# Integration_board_3204.net
KiCad netlist of a schematic drawn in EAGLE
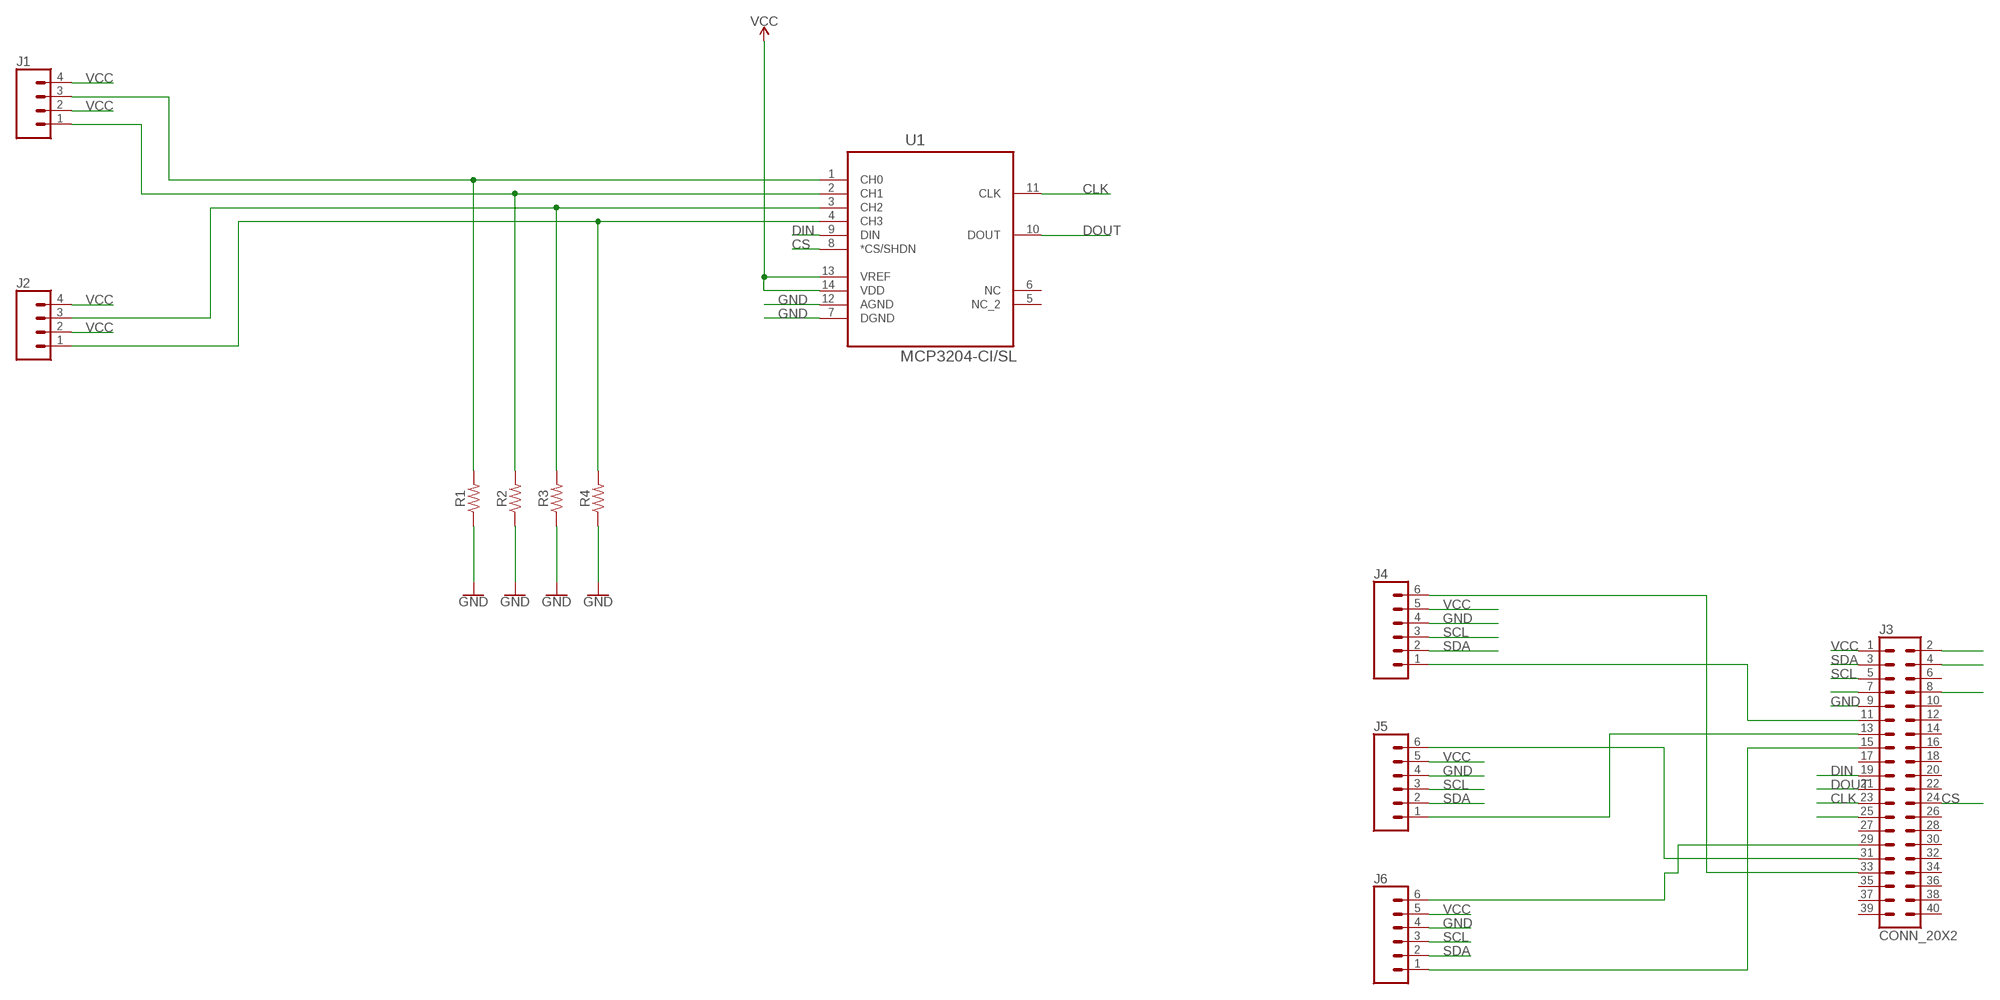
[diagram p0: schematic, sheet 1]

(export (version "E")
  (design (tool "Eeschema 10.0.6"))
  (components
    (comp (ref "J1")
      (value "CONN_04PTH")
      (footprint "eagle-import:1X04")
      (libsource (lib "eagle-import") (part "CONN_04PTH"))
    )
    (comp (ref "J2")
      (value "CONN_04PTH")
      (footprint "eagle-import:1X04")
      (libsource (lib "eagle-import") (part "CONN_04PTH"))
    )
    (comp (ref "J3")
      (value "CONN_20X2")
      (footprint "eagle-import:2X20")
      (libsource (lib "eagle-import") (part "CONN_20X2"))
    )
    (comp (ref "J4")
      (value "CONN_06SILK_FEMALE_PTH")
      (footprint "eagle-import:1X06")
      (libsource (lib "eagle-import") (part "CONN_06SILK_FEMALE_PTH"))
    )
    (comp (ref "J5")
      (value "CONN_06SILK_FEMALE_PTH")
      (footprint "eagle-import:1X06")
      (libsource (lib "eagle-import") (part "CONN_06SILK_FEMALE_PTH"))
    )
    (comp (ref "J6")
      (value "CONN_06SILK_FEMALE_PTH")
      (footprint "eagle-import:1X06")
      (libsource (lib "eagle-import") (part "CONN_06SILK_FEMALE_PTH"))
    )
    (comp (ref "R1")
      (value "RESISTORAXIAL-0.3")
      (footprint "eagle-import:AXIAL-0.3")
      (libsource (lib "eagle-import") (part "RESISTORAXIAL-0.3"))
    )
    (comp (ref "R2")
      (value "RESISTORAXIAL-0.3")
      (footprint "eagle-import:AXIAL-0.3")
      (libsource (lib "eagle-import") (part "RESISTORAXIAL-0.3"))
    )
    (comp (ref "R3")
      (value "RESISTORAXIAL-0.3")
      (footprint "eagle-import:AXIAL-0.3")
      (libsource (lib "eagle-import") (part "RESISTORAXIAL-0.3"))
    )
    (comp (ref "R4")
      (value "RESISTORAXIAL-0.3")
      (footprint "eagle-import:AXIAL-0.3")
      (libsource (lib "eagle-import") (part "RESISTORAXIAL-0.3"))
    )
    (comp (ref "U1")
      (value "MCP3204-CI/SL")
      (footprint "eagle-import:SOIC127P600X175-14N")
      (libsource (lib "eagle-import") (part "MCP3204-CI/SL"))
    )
  )
  (nets
    (net (code "1") (name "/CLK") (class "Default")
      (node (ref "J3") (pin "23") (pinfunction "23_23") (pintype "passive"))
      (node (ref "U1") (pin "11") (pinfunction "CLK_11") (pintype "input"))
    )
    (net (code "2") (name "/CS") (class "Default")
      (node (ref "J3") (pin "24") (pinfunction "24_24") (pintype "passive"))
      (node (ref "U1") (pin "8") (pinfunction "*CS/SHDN_8") (pintype "input"))
    )
    (net (code "3") (name "/DIN") (class "Default")
      (node (ref "J3") (pin "19") (pinfunction "19_19") (pintype "passive"))
      (node (ref "U1") (pin "9") (pinfunction "DIN_9") (pintype "input"))
    )
    (net (code "4") (name "/DOUT") (class "Default")
      (node (ref "J3") (pin "21") (pinfunction "21_21") (pintype "passive"))
      (node (ref "U1") (pin "10") (pinfunction "DOUT_10") (pintype "output"))
    )
    (net (code "5") (name "/SCL") (class "Default")
      (node (ref "J3") (pin "5") (pinfunction "5_5") (pintype "passive"))
      (node (ref "J4") (pin "3") (pinfunction "3_3") (pintype "passive"))
      (node (ref "J5") (pin "3") (pinfunction "3_3") (pintype "passive"))
      (node (ref "J6") (pin "3") (pinfunction "3_3") (pintype "passive"))
    )
    (net (code "6") (name "/SDA") (class "Default")
      (node (ref "J3") (pin "3") (pinfunction "3_3") (pintype "passive"))
      (node (ref "J4") (pin "2") (pinfunction "2_2") (pintype "passive"))
      (node (ref "J5") (pin "2") (pinfunction "2_2") (pintype "passive"))
      (node (ref "J6") (pin "2") (pinfunction "2_2") (pintype "passive"))
    )
    (net (code "7") (name "GND") (class "Default")
      (node (ref "J3") (pin "9") (pinfunction "9_9") (pintype "passive"))
      (node (ref "J4") (pin "4") (pinfunction "4_4") (pintype "passive"))
      (node (ref "J5") (pin "4") (pinfunction "4_4") (pintype "passive"))
      (node (ref "J6") (pin "4") (pinfunction "4_4") (pintype "passive"))
      (node (ref "R1") (pin "P$1") (pinfunction "1_P$1") (pintype "passive"))
      (node (ref "R2") (pin "P$1") (pinfunction "1_P$1") (pintype "passive"))
      (node (ref "R3") (pin "P$1") (pinfunction "1_P$1") (pintype "passive"))
      (node (ref "R4") (pin "P$1") (pinfunction "1_P$1") (pintype "passive"))
      (node (ref "U1") (pin "12") (pinfunction "AGND_12") (pintype "passive"))
      (node (ref "U1") (pin "7") (pinfunction "DGND_7") (pintype "passive"))
    )
    (net (code "8") (name "Net-(J3-Pad11)") (class "Default")
      (node (ref "J3") (pin "11") (pinfunction "11_11") (pintype "passive"))
      (node (ref "J4") (pin "1") (pinfunction "1_1") (pintype "passive"))
    )
    (net (code "9") (name "Net-(J3-Pad13)") (class "Default")
      (node (ref "J3") (pin "13") (pinfunction "13_13") (pintype "passive"))
      (node (ref "J5") (pin "1") (pinfunction "1_1") (pintype "passive"))
    )
    (net (code "10") (name "Net-(J3-Pad15)") (class "Default")
      (node (ref "J3") (pin "15") (pinfunction "15_15") (pintype "passive"))
      (node (ref "J6") (pin "1") (pinfunction "1_1") (pintype "passive"))
    )
    (net (code "11") (name "Net-(J3-Pad29)") (class "Default")
      (node (ref "J3") (pin "29") (pinfunction "29_29") (pintype "passive"))
      (node (ref "J6") (pin "6") (pinfunction "6_6") (pintype "passive"))
    )
    (net (code "12") (name "Net-(J3-Pad31)") (class "Default")
      (node (ref "J3") (pin "31") (pinfunction "31_31") (pintype "passive"))
      (node (ref "J5") (pin "6") (pinfunction "6_6") (pintype "passive"))
    )
    (net (code "13") (name "Net-(J3-Pad33)") (class "Default")
      (node (ref "J3") (pin "33") (pinfunction "33_33") (pintype "passive"))
      (node (ref "J4") (pin "6") (pinfunction "6_6") (pintype "passive"))
    )
    (net (code "14") (name "Net-(R1-2)") (class "Default")
      (node (ref "J1") (pin "3") (pinfunction "3_3") (pintype "passive"))
      (node (ref "R1") (pin "P$2") (pinfunction "2_P$2") (pintype "passive"))
      (node (ref "U1") (pin "1") (pinfunction "CH0_1") (pintype "input"))
    )
    (net (code "15") (name "Net-(R2-2)") (class "Default")
      (node (ref "J1") (pin "1") (pinfunction "1_1") (pintype "passive"))
      (node (ref "R2") (pin "P$2") (pinfunction "2_P$2") (pintype "passive"))
      (node (ref "U1") (pin "2") (pinfunction "CH1_2") (pintype "input"))
    )
    (net (code "16") (name "Net-(R3-2)") (class "Default")
      (node (ref "J2") (pin "3") (pinfunction "3_3") (pintype "passive"))
      (node (ref "R3") (pin "P$2") (pinfunction "2_P$2") (pintype "passive"))
      (node (ref "U1") (pin "3") (pinfunction "CH2_3") (pintype "input"))
    )
    (net (code "17") (name "Net-(R4-2)") (class "Default")
      (node (ref "J2") (pin "1") (pinfunction "1_1") (pintype "passive"))
      (node (ref "R4") (pin "P$2") (pinfunction "2_P$2") (pintype "passive"))
      (node (ref "U1") (pin "4") (pinfunction "CH3_4") (pintype "input"))
    )
    (net (code "18") (name "VCC") (class "Default")
      (node (ref "J1") (pin "2") (pinfunction "2_2") (pintype "passive"))
      (node (ref "J1") (pin "4") (pinfunction "4_4") (pintype "passive"))
      (node (ref "J2") (pin "2") (pinfunction "2_2") (pintype "passive"))
      (node (ref "J2") (pin "4") (pinfunction "4_4") (pintype "passive"))
      (node (ref "J3") (pin "1") (pinfunction "1_1") (pintype "passive"))
      (node (ref "J4") (pin "5") (pinfunction "5_5") (pintype "passive"))
      (node (ref "J5") (pin "5") (pinfunction "5_5") (pintype "passive"))
      (node (ref "J6") (pin "5") (pinfunction "5_5") (pintype "passive"))
      (node (ref "U1") (pin "13") (pinfunction "VREF_13") (pintype "input"))
      (node (ref "U1") (pin "14") (pinfunction "VDD_14") (pintype "power_in"))
    )
    (net (code "19") (name "unconnected-(J3-Pad2)") (class "Default")
      (node (ref "J3") (pin "2") (pinfunction "2_2") (pintype "passive"))
    )
    (net (code "20") (name "unconnected-(J3-Pad4)") (class "Default")
      (node (ref "J3") (pin "4") (pinfunction "4_4") (pintype "passive"))
    )
    (net (code "21") (name "unconnected-(J3-Pad6)") (class "Default")
      (node (ref "J3") (pin "6") (pinfunction "6_6") (pintype "passive"))
    )
    (net (code "22") (name "unconnected-(J3-Pad7)") (class "Default")
      (node (ref "J3") (pin "7") (pinfunction "7_7") (pintype "passive"))
    )
    (net (code "23") (name "unconnected-(J3-Pad8)") (class "Default")
      (node (ref "J3") (pin "8") (pinfunction "8_8") (pintype "passive"))
    )
    (net (code "24") (name "unconnected-(J3-Pad10)") (class "Default")
      (node (ref "J3") (pin "10") (pinfunction "10_10") (pintype "passive"))
    )
    (net (code "25") (name "unconnected-(J3-Pad12)") (class "Default")
      (node (ref "J3") (pin "12") (pinfunction "12_12") (pintype "passive"))
    )
    (net (code "26") (name "unconnected-(J3-Pad14)") (class "Default")
      (node (ref "J3") (pin "14") (pinfunction "14_14") (pintype "passive"))
    )
    (net (code "27") (name "unconnected-(J3-Pad16)") (class "Default")
      (node (ref "J3") (pin "16") (pinfunction "16_16") (pintype "passive"))
    )
    (net (code "28") (name "unconnected-(J3-Pad17)") (class "Default")
      (node (ref "J3") (pin "17") (pinfunction "17_17") (pintype "passive"))
    )
    (net (code "29") (name "unconnected-(J3-Pad18)") (class "Default")
      (node (ref "J3") (pin "18") (pinfunction "18_18") (pintype "passive"))
    )
    (net (code "30") (name "unconnected-(J3-Pad20)") (class "Default")
      (node (ref "J3") (pin "20") (pinfunction "20_20") (pintype "passive"))
    )
    (net (code "31") (name "unconnected-(J3-Pad22)") (class "Default")
      (node (ref "J3") (pin "22") (pinfunction "22_22") (pintype "passive"))
    )
    (net (code "32") (name "unconnected-(J3-Pad25)") (class "Default")
      (node (ref "J3") (pin "25") (pinfunction "25_25") (pintype "passive"))
    )
    (net (code "33") (name "unconnected-(J3-Pad26)") (class "Default")
      (node (ref "J3") (pin "26") (pinfunction "26_26") (pintype "passive"))
    )
    (net (code "34") (name "unconnected-(J3-Pad27)") (class "Default")
      (node (ref "J3") (pin "27") (pinfunction "27_27") (pintype "passive"))
    )
    (net (code "35") (name "unconnected-(J3-Pad28)") (class "Default")
      (node (ref "J3") (pin "28") (pinfunction "28_28") (pintype "passive"))
    )
    (net (code "36") (name "unconnected-(J3-Pad30)") (class "Default")
      (node (ref "J3") (pin "30") (pinfunction "30_30") (pintype "passive"))
    )
    (net (code "37") (name "unconnected-(J3-Pad32)") (class "Default")
      (node (ref "J3") (pin "32") (pinfunction "32_32") (pintype "passive"))
    )
    (net (code "38") (name "unconnected-(J3-Pad34)") (class "Default")
      (node (ref "J3") (pin "34") (pinfunction "34_34") (pintype "passive"))
    )
    (net (code "39") (name "unconnected-(J3-Pad35)") (class "Default")
      (node (ref "J3") (pin "35") (pinfunction "35_35") (pintype "passive"))
    )
    (net (code "40") (name "unconnected-(J3-Pad36)") (class "Default")
      (node (ref "J3") (pin "36") (pinfunction "36_36") (pintype "passive"))
    )
    (net (code "41") (name "unconnected-(J3-Pad37)") (class "Default")
      (node (ref "J3") (pin "37") (pinfunction "37_37") (pintype "passive"))
    )
    (net (code "42") (name "unconnected-(J3-Pad38)") (class "Default")
      (node (ref "J3") (pin "38") (pinfunction "38_38") (pintype "passive"))
    )
    (net (code "43") (name "unconnected-(J3-Pad39)") (class "Default")
      (node (ref "J3") (pin "39") (pinfunction "39_39") (pintype "passive"))
    )
    (net (code "44") (name "unconnected-(J3-Pad40)") (class "Default")
      (node (ref "J3") (pin "40") (pinfunction "40_40") (pintype "passive"))
    )
    (net (code "45") (name "unconnected-(U1-NC-Pad6)") (class "Default")
      (node (ref "U1") (pin "6") (pinfunction "NC_6") (pintype "no_connect"))
    )
    (net (code "46") (name "unconnected-(U1-NC_2-Pad5)") (class "Default")
      (node (ref "U1") (pin "5") (pinfunction "NC_2_5") (pintype "no_connect"))
    )
  )
)
